# BUCK_shematics.net
KiCad netlist of a schematic drawn in Altium Designer
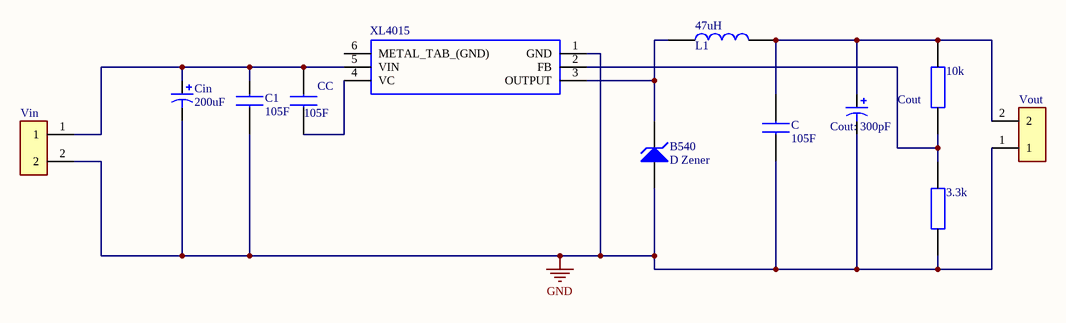
[diagram p0: BUCK_shematics.SchDoc]

(export (version "E")
  (design (tool "Eeschema 10.0.6"))
  (components
    (comp (ref "3.3k")
      (value "~")
      (footprint "RESC2012X65N")
      (description "Thick Film Resistors - SMD 0805 510Kohm 1% High VoltageAEC-Q200")
      (fields (field (name "MANUFACTURER_PART_NUMBER") "KTR10EZPF5103"))
      (libsource (lib "KTR10EZPF5103") (part "KTR10EZPF5103"))
    )
    (comp (ref "10k")
      (value "~")
      (footprint "RESC2012X65N")
      (description "Thick Film Resistors - SMD 0805 510Kohm 1% High VoltageAEC-Q200")
      (fields (field (name "MANUFACTURER_PART_NUMBER") "KTR10EZPF5103"))
      (libsource (lib "KTR10EZPF5103") (part "KTR10EZPF5103"))
    )
    (comp (ref "47uH")
      (value "L1")
      (footprint "INDPM110100X400N")
      (fields
        (field (name "MANUFACTURER_PART_NUMBER") "SRP1038A-470M")
        (field (name "RS PART NUMBER") "1728637")
      )
      (libsource (lib "SRP1038A-470M") (part "SRP1038A-470M"))
    )
    (comp (ref "105F")
      (value "CC")
      (footprint "CAPC2012X145N")
      (description "Multilayer Ceramic Capacitors MLCC - SMD/SMT 0805 0.1uF 50volts X7R 5%")
      (fields (field (name "MANUFACTURER_PART_NUMBER") "GRM21BR71H104JA01L"))
      (libsource (lib "GRM21BR71H104JA01L") (part "GRM21BR71H104JA01L"))
    )
    (comp (ref "B540")
      (value "D Zener")
      (footprint "DIODE-0.7")
      (description "Zener Diode")
      (fields (field (name "PUBLISHER") "Altium Limited"))
      (libsource (lib "Miscellaneous Devices") (part "D Zener"))
    )
    (comp (ref "C")
      (value "105F")
      (footprint "CAPC2012X145N")
      (description "Multilayer Ceramic Capacitors MLCC - SMD/SMT 0805 0.1uF 50volts X7R 5%")
      (fields (field (name "MANUFACTURER_PART_NUMBER") "GRM21BR71H104JA01L"))
      (libsource (lib "GRM21BR71H104JA01L") (part "GRM21BR71H104JA01L"))
    )
    (comp (ref "C1")
      (value "105F")
      (footprint "CAPC2012X145N")
      (description "Multilayer Ceramic Capacitors MLCC - SMD/SMT 0805 0.1uF 50volts X7R 5%")
      (fields (field (name "MANUFACTURER_PART_NUMBER") "GRM21BR71H104JA01L"))
      (libsource (lib "GRM21BR71H104JA01L") (part "GRM21BR71H104JA01L"))
    )
    (comp (ref "Cin")
      (value "200uF")
      (footprint "RB7.6-15")
      (description "Polarized Capacitor (Radial)")
      (fields (field (name "PUBLISHER") "Altium Limited"))
      (libsource (lib "Miscellaneous Devices") (part "Cap Pol1"))
    )
    (comp (ref "Cout")
      (value "Cin")
      (footprint "RB7.6-15")
      (description "Polarized Capacitor (Radial)")
      (fields (field (name "COUT") "300pF") (field (name "PUBLISHER") "Altium Limited"))
      (libsource (lib "Miscellaneous Devices") (part "Cap Pol1"))
    )
    (comp (ref "Vin")
      (value "~")
      (footprint "TE_794120-1")
      (description "Conn Power HDR 2 POS 5.08mm Solder RA Thru-Hole 2 Terminal 1 Port Automotive Bag")
      (fields (field (name "MF") "TE Connectivity") (field (name "MP") "794120-1"))
      (libsource (lib "794120-1") (part "794120-1"))
    )
    (comp (ref "Vout")
      (value "794120-1")
      (footprint "TE_794120-1")
      (description "Conn Power HDR 2 POS 5.08mm Solder RA Thru-Hole 2 Terminal 1 Port Automotive Bag")
      (fields (field (name "MF") "TE Connectivity"))
      (libsource (lib "") (part "794120-1_1"))
    )
    (comp (ref "XL4015")
      (value "~")
      (footprint "TO-263-5")
      (description "DC / DC converters in the housing TO263-5L, Voltage Regulator, Buck Converter, Switching Regulator")
      (fields (field (name "MANUFACTURER_PART_NUMBER") "AP1506-50K5G-13"))
      (libsource (lib "AP1506-50K5G-13") (part "AP1506-50K5G-13"))
    )
  )
  (nets
    (net (code "1") (name "GND") (class "Default")
      (node (ref "3.3k") (pin "1") (pinfunction "1_1") (pintype "passive"))
      (node (ref "B540") (pin "1") (pinfunction "A_1") (pintype "passive"))
      (node (ref "C") (pin "1") (pinfunction "1_1") (pintype "passive"))
      (node (ref "C1") (pin "1") (pinfunction "1_1") (pintype "passive"))
      (node (ref "Cin") (pin "2") (pinfunction "2_2") (pintype "passive"))
      (node (ref "Cout") (pin "2") (pinfunction "2_2") (pintype "passive"))
      (node (ref "Vin") (pin "2") (pinfunction "2_2") (pintype "passive"))
      (node (ref "Vout") (pin "1") (pinfunction "1_1") (pintype "passive"))
      (node (ref "XL4015") (pin "1") (pinfunction "GND_1") (pintype "passive"))
    )
    (net (code "2") (name "Net-(10k-Pad2)") (class "Default")
      (node (ref "10k") (pin "2") (pinfunction "2_2") (pintype "passive"))
      (node (ref "47uH") (pin "2") (pinfunction "2_2") (pintype "passive"))
      (node (ref "C") (pin "2") (pinfunction "2_2") (pintype "passive"))
      (node (ref "Cout") (pin "1") (pinfunction "1_1") (pintype "passive"))
      (node (ref "Vout") (pin "2") (pinfunction "2_2") (pintype "passive"))
    )
    (net (code "3") (name "Net-(B540-K)") (class "Default")
      (node (ref "47uH") (pin "1") (pinfunction "1_1") (pintype "passive"))
      (node (ref "B540") (pin "2") (pinfunction "K_2") (pintype "passive"))
      (node (ref "XL4015") (pin "3") (pinfunction "OUTPUT_3") (pintype "passive"))
    )
    (net (code "4") (name "Net-(XL4015-FB)") (class "Default")
      (node (ref "10k") (pin "1") (pinfunction "1_1") (pintype "passive"))
      (node (ref "3.3k") (pin "2") (pinfunction "2_2") (pintype "passive"))
      (node (ref "XL4015") (pin "2") (pinfunction "FB_2") (pintype "passive"))
    )
    (net (code "5") (name "Net-(XL4015-VC)") (class "Default")
      (node (ref "105F") (pin "1") (pinfunction "1_1") (pintype "passive"))
      (node (ref "XL4015") (pin "4") (pinfunction "VC_4") (pintype "passive"))
    )
    (net (code "6") (name "Net-(XL4015-VIN)") (class "Default")
      (node (ref "105F") (pin "2") (pinfunction "2_2") (pintype "passive"))
      (node (ref "C1") (pin "2") (pinfunction "2_2") (pintype "passive"))
      (node (ref "Cin") (pin "1") (pinfunction "1_1") (pintype "passive"))
      (node (ref "Vin") (pin "1") (pinfunction "1_1") (pintype "passive"))
      (node (ref "XL4015") (pin "5") (pinfunction "VIN_5") (pintype "passive"))
    )
    (net (code "7") (name "unconnected-(XL4015-METAL_TAB_(GND)-Pad6)") (class "Default")
      (node (ref "XL4015") (pin "6") (pinfunction "METAL_TAB_(GND)_6") (pintype "passive"))
    )
  )
)
